# Shifting_microSD.net
KiCad netlist of a schematic drawn in EAGLE
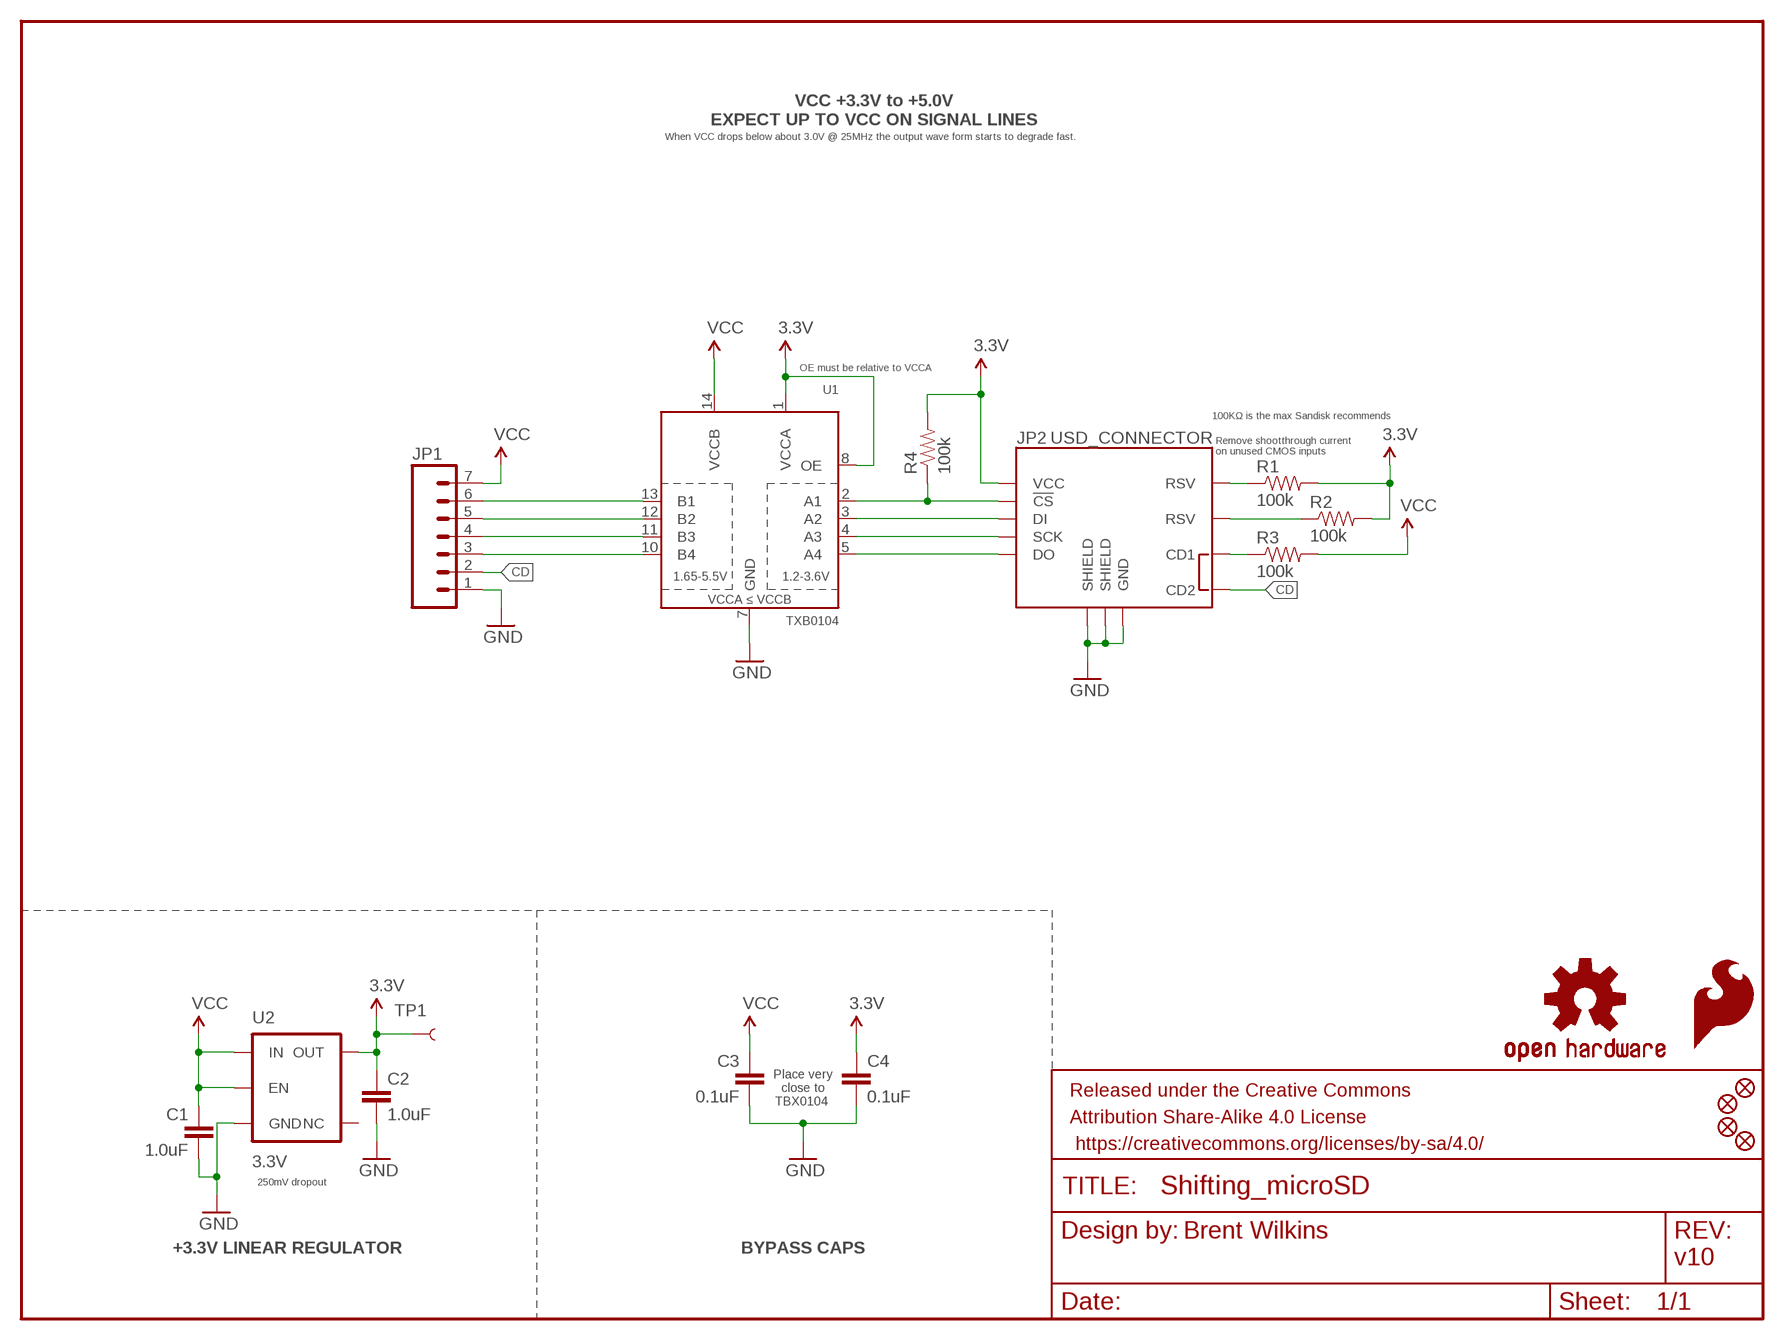
[diagram p0: schematic, sheet 1]

(export (version "E")
  (design (tool "Eeschema 10.0.6"))
  (components
    (comp (ref "C1")
      (value "1.0uF")
      (footprint "eagle-import:0603-CAP")
      (libsource (lib "eagle-import") (part "1.0UF-16V-10%(0603)"))
    )
    (comp (ref "C2")
      (value "1.0uF")
      (footprint "eagle-import:0603-CAP")
      (libsource (lib "eagle-import") (part "1.0UF-16V-10%(0603)"))
    )
    (comp (ref "C3")
      (value "0.1uF")
      (footprint "eagle-import:0603-CAP")
      (libsource (lib "eagle-import") (part "0.1UF-25V(+80/-20%)(0603)"))
    )
    (comp (ref "C4")
      (value "0.1uF")
      (footprint "eagle-import:0603-CAP")
      (libsource (lib "eagle-import") (part "0.1UF-25V(+80/-20%)(0603)"))
    )
    (comp (ref "FID1")
      (value "FIDUCIAL1X2")
      (footprint "eagle-import:FIDUCIAL-1X2")
      (libsource (lib "eagle-import") (part "FIDUCIAL1X2"))
    )
    (comp (ref "FID2")
      (value "FIDUCIAL1X2")
      (footprint "eagle-import:FIDUCIAL-1X2")
      (libsource (lib "eagle-import") (part "FIDUCIAL1X2"))
    )
    (comp (ref "FID3")
      (value "FIDUCIAL1X2")
      (footprint "eagle-import:FIDUCIAL-1X2")
      (libsource (lib "eagle-import") (part "FIDUCIAL1X2"))
    )
    (comp (ref "FID4")
      (value "FIDUCIAL1X2")
      (footprint "eagle-import:FIDUCIAL-1X2")
      (libsource (lib "eagle-import") (part "FIDUCIAL1X2"))
    )
    (comp (ref "FRAME1")
      (value "FRAME-LETTER")
      (footprint "eagle-import:CREATIVE_COMMONS")
      (libsource (lib "eagle-import") (part "FRAME-LETTER"))
    )
    (comp (ref "JP1")
      (value "M07")
      (footprint "eagle-import:1X07")
      (libsource (lib "eagle-import") (part "M07"))
    )
    (comp (ref "JP2")
      (value "USD_CONNECTOR")
      (footprint "eagle-import:MICRO-SD-SOCKET-PP")
      (libsource (lib "eagle-import") (part "USD_CONNECTOR"))
    )
    (comp (ref "LOGO1")
      (value "SFE_LOGO_FLAME.2_INCH")
      (footprint "eagle-import:SFE_LOGO_FLAME_.2")
      (libsource (lib "eagle-import") (part "SFE_LOGO_FLAME.2_INCH"))
    )
    (comp (ref "LOGO2")
      (value "OSHW-LOGOS")
      (footprint "eagle-import:OSHW-LOGO-S")
      (libsource (lib "eagle-import") (part "OSHW-LOGOS"))
    )
    (comp (ref "R1")
      (value "100k")
      (footprint "eagle-import:0603-RES")
      (libsource (lib "eagle-import") (part "100KOHM-1/10W-1%(0603)"))
    )
    (comp (ref "R2")
      (value "100k")
      (footprint "eagle-import:0603-RES")
      (libsource (lib "eagle-import") (part "100KOHM-1/10W-1%(0603)"))
    )
    (comp (ref "R3")
      (value "100k")
      (footprint "eagle-import:0603-RES")
      (libsource (lib "eagle-import") (part "100KOHM-1/10W-1%(0603)"))
    )
    (comp (ref "R4")
      (value "100k")
      (footprint "eagle-import:0603-RES")
      (libsource (lib "eagle-import") (part "100KOHM-1/10W-1%(0603)"))
    )
    (comp (ref "TP1")
      (value "TEST-POINT3")
      (footprint "eagle-import:PAD.03X.03")
      (libsource (lib "eagle-import") (part "TEST-POINT3"))
    )
    (comp (ref "U1")
      (value "TXB0104")
      (footprint "eagle-import:SO14")
      (libsource (lib "eagle-import") (part "TXB0104PWRSOIC14"))
    )
    (comp (ref "U2")
      (value "3.3V")
      (footprint "eagle-import:SOT23-5")
      (libsource (lib "eagle-import") (part "V_REG_AP2112K-3.3V"))
    )
  )
  (nets
    (net (code "1") (name "3.3V") (class "Default")
      (node (ref "C2") (pin "1") (pinfunction "1_1") (pintype "passive"))
      (node (ref "C4") (pin "1") (pinfunction "1_1") (pintype "passive"))
      (node (ref "JP2") (pin "VCC") (pinfunction "VCC_VCC") (pintype "bidirectional"))
      (node (ref "R1") (pin "2") (pinfunction "2_2") (pintype "passive"))
      (node (ref "R2") (pin "2") (pinfunction "2_2") (pintype "passive"))
      (node (ref "R4") (pin "2") (pinfunction "2_2") (pintype "passive"))
      (node (ref "TP1") (pin "P$1") (pinfunction "1_P$1") (pintype "bidirectional"))
      (node (ref "U1") (pin "1") (pinfunction "VCCA_1") (pintype "bidirectional"))
      (node (ref "U1") (pin "8") (pinfunction "OE_8") (pintype "bidirectional"))
      (node (ref "U2") (pin "5") (pinfunction "OUT_5") (pintype "passive"))
    )
    (net (code "2") (name "CD") (class "Default")
      (node (ref "JP1") (pin "2") (pinfunction "2_2") (pintype "passive"))
      (node (ref "JP2") (pin "CD2") (pinfunction "CD2_CD2") (pintype "bidirectional"))
    )
    (net (code "3") (name "GND") (class "Default")
      (node (ref "C1") (pin "2") (pinfunction "2_2") (pintype "passive"))
      (node (ref "C2") (pin "2") (pinfunction "2_2") (pintype "passive"))
      (node (ref "C3") (pin "2") (pinfunction "2_2") (pintype "passive"))
      (node (ref "C4") (pin "2") (pinfunction "2_2") (pintype "passive"))
      (node (ref "JP1") (pin "1") (pinfunction "1_1") (pintype "passive"))
      (node (ref "JP2") (pin "GND") (pinfunction "GND_GND") (pintype "bidirectional"))
      (node (ref "JP2") (pin "GND1") (pinfunction "SHIELD_GND1") (pintype "bidirectional"))
      (node (ref "JP2") (pin "GND3") (pinfunction "SHIELD_GND3") (pintype "bidirectional"))
      (node (ref "U1") (pin "7") (pinfunction "GND_7") (pintype "bidirectional"))
      (node (ref "U2") (pin "2") (pinfunction "GND_2") (pintype "input"))
    )
    (net (code "4") (name "Net-(JP2-PadCD1)") (class "Default")
      (node (ref "JP2") (pin "CD1") (pinfunction "CD1_CD1") (pintype "bidirectional"))
      (node (ref "R3") (pin "1") (pinfunction "1_1") (pintype "passive"))
    )
    (net (code "5") (name "Net-(JP2-RSV-PadRSV1)") (class "Default")
      (node (ref "JP2") (pin "RSV1") (pinfunction "RSV_RSV1") (pintype "bidirectional"))
      (node (ref "R1") (pin "1") (pinfunction "1_1") (pintype "passive"))
    )
    (net (code "6") (name "Net-(JP2-RSV-PadRSV2)") (class "Default")
      (node (ref "JP2") (pin "RSV2") (pinfunction "RSV_RSV2") (pintype "bidirectional"))
      (node (ref "R2") (pin "1") (pinfunction "1_1") (pintype "passive"))
    )
    (net (code "7") (name "Net-(JP2-SCK)") (class "Default")
      (node (ref "JP2") (pin "SCLK") (pinfunction "SCK_SCLK") (pintype "bidirectional"))
      (node (ref "U1") (pin "4") (pinfunction "A3_4") (pintype "bidirectional"))
    )
    (net (code "8") (name "Net-(JP2-~{CS})") (class "Default")
      (node (ref "JP2") (pin "CS") (pinfunction "~{CS}_CS") (pintype "bidirectional"))
      (node (ref "R4") (pin "1") (pinfunction "1_1") (pintype "passive"))
      (node (ref "U1") (pin "2") (pinfunction "A1_2") (pintype "bidirectional"))
    )
    (net (code "9") (name "Net-(U1-A2)") (class "Default")
      (node (ref "JP2") (pin "DI") (pinfunction "DI_DI") (pintype "bidirectional"))
      (node (ref "U1") (pin "3") (pinfunction "A2_3") (pintype "bidirectional"))
    )
    (net (code "10") (name "Net-(U1-A4)") (class "Default")
      (node (ref "JP2") (pin "DO") (pinfunction "DO_DO") (pintype "bidirectional"))
      (node (ref "U1") (pin "5") (pinfunction "A4_5") (pintype "bidirectional"))
    )
    (net (code "11") (name "Net-(U1-B1)") (class "Default")
      (node (ref "JP1") (pin "6") (pinfunction "6_6") (pintype "passive"))
      (node (ref "U1") (pin "13") (pinfunction "B1_13") (pintype "bidirectional"))
    )
    (net (code "12") (name "Net-(U1-B2)") (class "Default")
      (node (ref "JP1") (pin "5") (pinfunction "5_5") (pintype "passive"))
      (node (ref "U1") (pin "12") (pinfunction "B2_12") (pintype "bidirectional"))
    )
    (net (code "13") (name "Net-(U1-B3)") (class "Default")
      (node (ref "JP1") (pin "4") (pinfunction "4_4") (pintype "passive"))
      (node (ref "U1") (pin "11") (pinfunction "B3_11") (pintype "bidirectional"))
    )
    (net (code "14") (name "Net-(U1-B4)") (class "Default")
      (node (ref "JP1") (pin "3") (pinfunction "3_3") (pintype "passive"))
      (node (ref "U1") (pin "10") (pinfunction "B4_10") (pintype "bidirectional"))
    )
    (net (code "15") (name "VCC") (class "Default")
      (node (ref "C1") (pin "1") (pinfunction "1_1") (pintype "passive"))
      (node (ref "C3") (pin "1") (pinfunction "1_1") (pintype "passive"))
      (node (ref "JP1") (pin "7") (pinfunction "7_7") (pintype "passive"))
      (node (ref "R3") (pin "2") (pinfunction "2_2") (pintype "passive"))
      (node (ref "U1") (pin "14") (pinfunction "VCCB_14") (pintype "bidirectional"))
      (node (ref "U2") (pin "1") (pinfunction "IN_1") (pintype "input"))
      (node (ref "U2") (pin "3") (pinfunction "EN_3") (pintype "input"))
    )
    (net (code "16") (name "unconnected-(U2-NC-Pad4)") (class "Default")
      (node (ref "U2") (pin "4") (pinfunction "NC_4") (pintype "input"))
    )
  )
)
